# EasyEDA_Walrusgand_Projectfile.net
KiCad netlist of a schematic drawn in EasyEDA
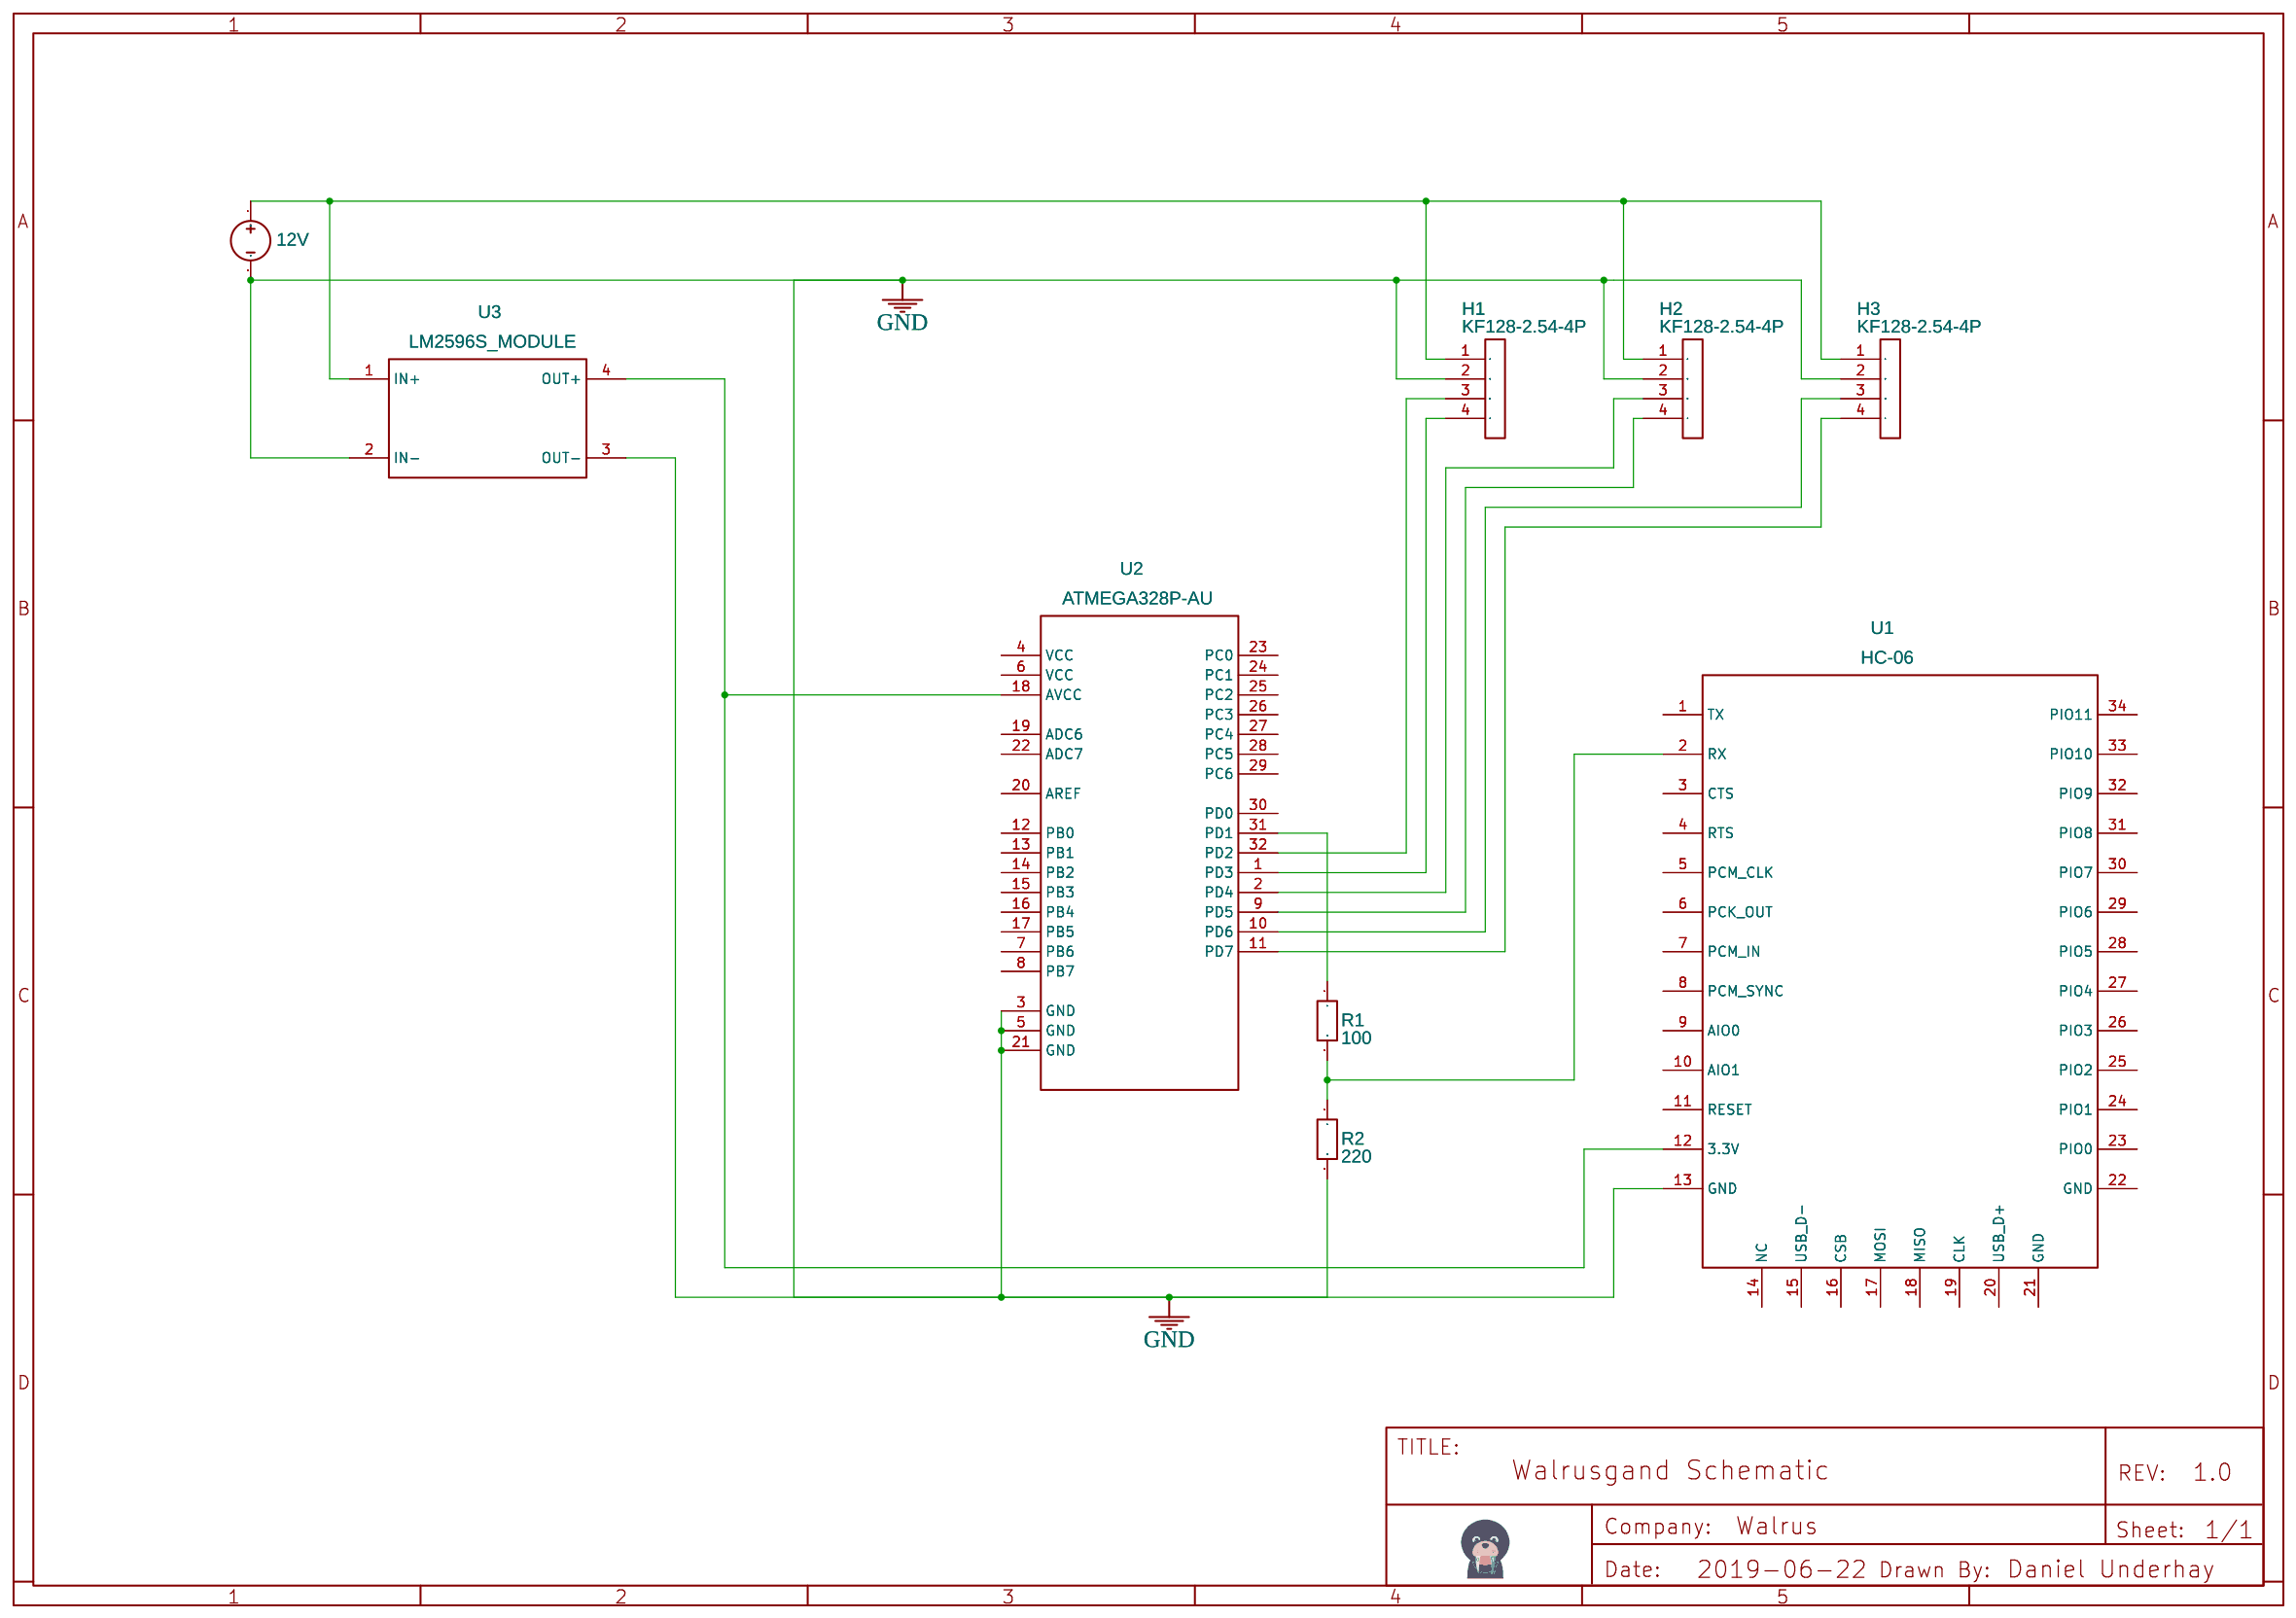
[diagram p0: schematic sheet]

(export (version "E")
  (design (tool "Eeschema 10.0.6"))
  (components
    (comp (ref "12V")
      (value "SIN(5) AC 1 0")
      (fields (field (name "BOM_Manufacturer Part") "?"))
      (libsource (lib "") (part "Vsin"))
    )
    (comp (ref "H1") (value "KF128-2.54-4P") (libsource (lib "") (part "Unknown_745_185")))
    (comp (ref "H2") (value "KF128-2.54-4P") (libsource (lib "") (part "Unknown_845_185")))
    (comp (ref "H3") (value "KF128-2.54-4P") (libsource (lib "") (part "Unknown_945_185")))
    (comp (ref "R1")
      (value "100")
      (fields (field (name "BOM_Manufacturer Part") "?"))
      (libsource (lib "") (part "Res_0603(1/10W)_EU"))
    )
    (comp (ref "R2")
      (value "220")
      (fields (field (name "BOM_Manufacturer Part") "?"))
      (libsource (lib "") (part "Res_0603(1/10W)_EU"))
    )
    (comp (ref "U1")
      (value "HC-06")
      (fields (field (name "BOM_Manufacturer Part") "hc06"))
      (libsource (lib "") (part "Unknown_855_385"))
    )
    (comp (ref "U2")
      (value "ATMEGA328P-AU")
      (fields (field (name "BOM_Supplier Part") "C14877"))
      (libsource (lib "") (part "Unknown_570_425"))
    )
    (comp (ref "U3")
      (value "LM2596S_MODULE")
      (fields (field (name "BOM_Manufacturer Part") "?"))
      (libsource (lib "") (part "Unknown_240_205"))
    )
  )
  (nets
    (net (code "1") (name "GND") (class "Default")
      (node (ref "12V") (pin "2") (pinfunction "2_2") (pintype "unspecified"))
      (node (ref "H1") (pin "2") (pinfunction "2_2") (pintype "unspecified"))
      (node (ref "H2") (pin "2") (pinfunction "2_2") (pintype "unspecified"))
      (node (ref "H3") (pin "2") (pinfunction "2_2") (pintype "unspecified"))
      (node (ref "R2") (pin "2") (pinfunction "2_2") (pintype "unspecified"))
      (node (ref "U1") (pin "13") (pinfunction "GND_13") (pintype "unspecified"))
      (node (ref "U2") (pin "21") (pinfunction "GND_21") (pintype "unspecified"))
      (node (ref "U2") (pin "3") (pinfunction "GND_3") (pintype "unspecified"))
      (node (ref "U2") (pin "5") (pinfunction "GND_5") (pintype "unspecified"))
      (node (ref "U3") (pin "2") (pinfunction "IN-_2") (pintype "unspecified"))
      (node (ref "U3") (pin "3") (pinfunction "OUT-_3") (pintype "unspecified"))
    )
    (net (code "2") (name "Net-(U1-3.3V)") (class "Default")
      (node (ref "U1") (pin "12") (pinfunction "3.3V_12") (pintype "unspecified"))
      (node (ref "U2") (pin "18") (pinfunction "AVCC_18") (pintype "passive"))
      (node (ref "U3") (pin "4") (pinfunction "OUT+_4") (pintype "unspecified"))
    )
    (net (code "3") (name "Net-(U1-RX)") (class "Default")
      (node (ref "R1") (pin "2") (pinfunction "2_2") (pintype "unspecified"))
      (node (ref "R2") (pin "1") (pinfunction "1_1") (pintype "unspecified"))
      (node (ref "U1") (pin "2") (pinfunction "RX_2") (pintype "unspecified"))
    )
    (net (code "4") (name "Net-(U2-PD1)") (class "Default")
      (node (ref "R1") (pin "1") (pinfunction "1_1") (pintype "unspecified"))
      (node (ref "U2") (pin "31") (pinfunction "PD1_31") (pintype "unspecified"))
    )
    (net (code "5") (name "Net-(U2-PD2)") (class "Default")
      (node (ref "H1") (pin "3") (pinfunction "3_3") (pintype "unspecified"))
      (node (ref "U2") (pin "32") (pinfunction "PD2_32") (pintype "unspecified"))
    )
    (net (code "6") (name "Net-(U2-PD3)") (class "Default")
      (node (ref "H1") (pin "4") (pinfunction "4_4") (pintype "unspecified"))
      (node (ref "U2") (pin "1") (pinfunction "PD3_1") (pintype "unspecified"))
    )
    (net (code "7") (name "Net-(U2-PD4)") (class "Default")
      (node (ref "H2") (pin "3") (pinfunction "3_3") (pintype "unspecified"))
      (node (ref "U2") (pin "2") (pinfunction "PD4_2") (pintype "unspecified"))
    )
    (net (code "8") (name "Net-(U2-PD5)") (class "Default")
      (node (ref "H2") (pin "4") (pinfunction "4_4") (pintype "unspecified"))
      (node (ref "U2") (pin "9") (pinfunction "PD5_9") (pintype "unspecified"))
    )
    (net (code "9") (name "Net-(U2-PD6)") (class "Default")
      (node (ref "H3") (pin "3") (pinfunction "3_3") (pintype "unspecified"))
      (node (ref "U2") (pin "10") (pinfunction "PD6_10") (pintype "unspecified"))
    )
    (net (code "10") (name "Net-(U2-PD7)") (class "Default")
      (node (ref "H3") (pin "4") (pinfunction "4_4") (pintype "unspecified"))
      (node (ref "U2") (pin "11") (pinfunction "PD7_11") (pintype "unspecified"))
    )
    (net (code "11") (name "Net-(U3-IN+)") (class "Default")
      (node (ref "12V") (pin "1") (pinfunction "1_1") (pintype "unspecified"))
      (node (ref "H1") (pin "1") (pinfunction "1_1") (pintype "unspecified"))
      (node (ref "H2") (pin "1") (pinfunction "1_1") (pintype "unspecified"))
      (node (ref "H3") (pin "1") (pinfunction "1_1") (pintype "unspecified"))
      (node (ref "U3") (pin "1") (pinfunction "IN+_1") (pintype "unspecified"))
    )
    (net (code "12") (name "unconnected-(U1-AIO0-Pad9)") (class "Default")
      (node (ref "U1") (pin "9") (pinfunction "AIO0_9") (pintype "unspecified"))
    )
    (net (code "13") (name "unconnected-(U1-AIO1-Pad10)") (class "Default")
      (node (ref "U1") (pin "10") (pinfunction "AIO1_10") (pintype "unspecified"))
    )
    (net (code "14") (name "unconnected-(U1-CLK-Pad19)") (class "Default")
      (node (ref "U1") (pin "19") (pinfunction "CLK_19") (pintype "unspecified"))
    )
    (net (code "15") (name "unconnected-(U1-CSB-Pad16)") (class "Default")
      (node (ref "U1") (pin "16") (pinfunction "CSB_16") (pintype "unspecified"))
    )
    (net (code "16") (name "unconnected-(U1-CTS-Pad3)") (class "Default")
      (node (ref "U1") (pin "3") (pinfunction "CTS_3") (pintype "unspecified"))
    )
    (net (code "17") (name "unconnected-(U1-GND-Pad21)") (class "Default")
      (node (ref "U1") (pin "21") (pinfunction "GND_21") (pintype "unspecified"))
    )
    (net (code "18") (name "unconnected-(U1-GND-Pad22)") (class "Default")
      (node (ref "U1") (pin "22") (pinfunction "GND_22") (pintype "unspecified"))
    )
    (net (code "19") (name "unconnected-(U1-MISO-Pad18)") (class "Default")
      (node (ref "U1") (pin "18") (pinfunction "MISO_18") (pintype "unspecified"))
    )
    (net (code "20") (name "unconnected-(U1-MOSI-Pad17)") (class "Default")
      (node (ref "U1") (pin "17") (pinfunction "MOSI_17") (pintype "unspecified"))
    )
    (net (code "21") (name "unconnected-(U1-NC-Pad14)") (class "Default")
      (node (ref "U1") (pin "14") (pinfunction "NC_14") (pintype "unspecified"))
    )
    (net (code "22") (name "unconnected-(U1-PCK_OUT-Pad6)") (class "Default")
      (node (ref "U1") (pin "6") (pinfunction "PCK_OUT_6") (pintype "unspecified"))
    )
    (net (code "23") (name "unconnected-(U1-PCM_CLK-Pad5)") (class "Default")
      (node (ref "U1") (pin "5") (pinfunction "PCM_CLK_5") (pintype "unspecified"))
    )
    (net (code "24") (name "unconnected-(U1-PCM_IN-Pad7)") (class "Default")
      (node (ref "U1") (pin "7") (pinfunction "PCM_IN_7") (pintype "unspecified"))
    )
    (net (code "25") (name "unconnected-(U1-PCM_SYNC-Pad8)") (class "Default")
      (node (ref "U1") (pin "8") (pinfunction "PCM_SYNC_8") (pintype "unspecified"))
    )
    (net (code "26") (name "unconnected-(U1-PIO0-Pad23)") (class "Default")
      (node (ref "U1") (pin "23") (pinfunction "PIO0_23") (pintype "unspecified"))
    )
    (net (code "27") (name "unconnected-(U1-PIO1-Pad24)") (class "Default")
      (node (ref "U1") (pin "24") (pinfunction "PIO1_24") (pintype "unspecified"))
    )
    (net (code "28") (name "unconnected-(U1-PIO2-Pad25)") (class "Default")
      (node (ref "U1") (pin "25") (pinfunction "PIO2_25") (pintype "unspecified"))
    )
    (net (code "29") (name "unconnected-(U1-PIO3-Pad26)") (class "Default")
      (node (ref "U1") (pin "26") (pinfunction "PIO3_26") (pintype "unspecified"))
    )
    (net (code "30") (name "unconnected-(U1-PIO4-Pad27)") (class "Default")
      (node (ref "U1") (pin "27") (pinfunction "PIO4_27") (pintype "unspecified"))
    )
    (net (code "31") (name "unconnected-(U1-PIO5-Pad28)") (class "Default")
      (node (ref "U1") (pin "28") (pinfunction "PIO5_28") (pintype "unspecified"))
    )
    (net (code "32") (name "unconnected-(U1-PIO6-Pad29)") (class "Default")
      (node (ref "U1") (pin "29") (pinfunction "PIO6_29") (pintype "unspecified"))
    )
    (net (code "33") (name "unconnected-(U1-PIO7-Pad30)") (class "Default")
      (node (ref "U1") (pin "30") (pinfunction "PIO7_30") (pintype "unspecified"))
    )
    (net (code "34") (name "unconnected-(U1-PIO8-Pad31)") (class "Default")
      (node (ref "U1") (pin "31") (pinfunction "PIO8_31") (pintype "unspecified"))
    )
    (net (code "35") (name "unconnected-(U1-PIO9-Pad32)") (class "Default")
      (node (ref "U1") (pin "32") (pinfunction "PIO9_32") (pintype "unspecified"))
    )
    (net (code "36") (name "unconnected-(U1-PIO10-Pad33)") (class "Default")
      (node (ref "U1") (pin "33") (pinfunction "PIO10_33") (pintype "unspecified"))
    )
    (net (code "37") (name "unconnected-(U1-PIO11-Pad34)") (class "Default")
      (node (ref "U1") (pin "34") (pinfunction "PIO11_34") (pintype "unspecified"))
    )
    (net (code "38") (name "unconnected-(U1-RESET-Pad11)") (class "Default")
      (node (ref "U1") (pin "11") (pinfunction "RESET_11") (pintype "unspecified"))
    )
    (net (code "39") (name "unconnected-(U1-RTS-Pad4)") (class "Default")
      (node (ref "U1") (pin "4") (pinfunction "RTS_4") (pintype "unspecified"))
    )
    (net (code "40") (name "unconnected-(U1-TX-Pad1)") (class "Default")
      (node (ref "U1") (pin "1") (pinfunction "TX_1") (pintype "unspecified"))
    )
    (net (code "41") (name "unconnected-(U1-USB_D+-Pad20)") (class "Default")
      (node (ref "U1") (pin "20") (pinfunction "USB_D+_20") (pintype "unspecified"))
    )
    (net (code "42") (name "unconnected-(U1-USB_D--Pad15)") (class "Default")
      (node (ref "U1") (pin "15") (pinfunction "USB_D-_15") (pintype "unspecified"))
    )
    (net (code "43") (name "unconnected-(U2-ADC6-Pad19)") (class "Default")
      (node (ref "U2") (pin "19") (pinfunction "ADC6_19") (pintype "input"))
    )
    (net (code "44") (name "unconnected-(U2-ADC7-Pad22)") (class "Default")
      (node (ref "U2") (pin "22") (pinfunction "ADC7_22") (pintype "input"))
    )
    (net (code "45") (name "unconnected-(U2-AREF-Pad20)") (class "Default")
      (node (ref "U2") (pin "20") (pinfunction "AREF_20") (pintype "input"))
    )
    (net (code "46") (name "unconnected-(U2-PB0-Pad12)") (class "Default")
      (node (ref "U2") (pin "12") (pinfunction "PB0_12") (pintype "unspecified"))
    )
    (net (code "47") (name "unconnected-(U2-PB1-Pad13)") (class "Default")
      (node (ref "U2") (pin "13") (pinfunction "PB1_13") (pintype "unspecified"))
    )
    (net (code "48") (name "unconnected-(U2-PB2-Pad14)") (class "Default")
      (node (ref "U2") (pin "14") (pinfunction "PB2_14") (pintype "unspecified"))
    )
    (net (code "49") (name "unconnected-(U2-PB3-Pad15)") (class "Default")
      (node (ref "U2") (pin "15") (pinfunction "PB3_15") (pintype "unspecified"))
    )
    (net (code "50") (name "unconnected-(U2-PB4-Pad16)") (class "Default")
      (node (ref "U2") (pin "16") (pinfunction "PB4_16") (pintype "unspecified"))
    )
    (net (code "51") (name "unconnected-(U2-PB5-Pad17)") (class "Default")
      (node (ref "U2") (pin "17") (pinfunction "PB5_17") (pintype "unspecified"))
    )
    (net (code "52") (name "unconnected-(U2-PB6-Pad7)") (class "Default")
      (node (ref "U2") (pin "7") (pinfunction "PB6_7") (pintype "unspecified"))
    )
    (net (code "53") (name "unconnected-(U2-PB7-Pad8)") (class "Default")
      (node (ref "U2") (pin "8") (pinfunction "PB7_8") (pintype "unspecified"))
    )
    (net (code "54") (name "unconnected-(U2-PC0-Pad23)") (class "Default")
      (node (ref "U2") (pin "23") (pinfunction "PC0_23") (pintype "unspecified"))
    )
    (net (code "55") (name "unconnected-(U2-PC1-Pad24)") (class "Default")
      (node (ref "U2") (pin "24") (pinfunction "PC1_24") (pintype "unspecified"))
    )
    (net (code "56") (name "unconnected-(U2-PC2-Pad25)") (class "Default")
      (node (ref "U2") (pin "25") (pinfunction "PC2_25") (pintype "unspecified"))
    )
    (net (code "57") (name "unconnected-(U2-PC3-Pad26)") (class "Default")
      (node (ref "U2") (pin "26") (pinfunction "PC3_26") (pintype "unspecified"))
    )
    (net (code "58") (name "unconnected-(U2-PC4-Pad27)") (class "Default")
      (node (ref "U2") (pin "27") (pinfunction "PC4_27") (pintype "unspecified"))
    )
    (net (code "59") (name "unconnected-(U2-PC5-Pad28)") (class "Default")
      (node (ref "U2") (pin "28") (pinfunction "PC5_28") (pintype "unspecified"))
    )
    (net (code "60") (name "unconnected-(U2-PC6-Pad29)") (class "Default")
      (node (ref "U2") (pin "29") (pinfunction "PC6_29") (pintype "unspecified"))
    )
    (net (code "61") (name "unconnected-(U2-PD0-Pad30)") (class "Default")
      (node (ref "U2") (pin "30") (pinfunction "PD0_30") (pintype "unspecified"))
    )
    (net (code "62") (name "unconnected-(U2-VCC-Pad4)") (class "Default")
      (node (ref "U2") (pin "4") (pinfunction "VCC_4") (pintype "passive"))
    )
    (net (code "63") (name "unconnected-(U2-VCC-Pad6)") (class "Default")
      (node (ref "U2") (pin "6") (pinfunction "VCC_6") (pintype "passive"))
    )
  )
)
